# BMP180.net
KiCad netlist of a schematic drawn in Altium Designer
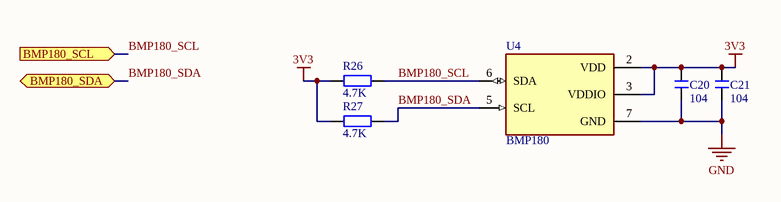
[diagram p0: BMP180气压传感器模块.SchDoc]

(export (version "E")
  (design (tool "Eeschema 10.0.6"))
  (components
    (comp (ref "C20")
      (value "104")
      (footprint "C 0603_L")
      (description "无极性贴片电容")
      (fields (field (name "版权归属") "黎明电子style"))
      (libsource (lib "3.3   - 电容capacitor") (part "C"))
    )
    (comp (ref "C21")
      (value "104")
      (footprint "C 0603_L")
      (description "无极性贴片电容")
      (fields (field (name "版权归属") "黎明电子style"))
      (libsource (lib "3.3   - 电容capacitor") (part "C"))
    )
    (comp (ref "R26")
      (value "4.7K")
      (footprint "R 0603_L")
      (description "贴片电阻")
      (fields (field (name "版权归属") "黎明电子style"))
      (libsource (lib "3.4   - 电阻Resistor") (part "R"))
    )
    (comp (ref "R27")
      (value "4.7K")
      (footprint "R 0603_L")
      (description "贴片电阻")
      (fields (field (name "版权归属") "黎明电子style"))
      (libsource (lib "3.4   - 电阻Resistor") (part "R"))
    )
    (comp (ref "U4")
      (value "BMP180")
      (footprint "LGA:LGA-7")
      (description "气压传感器Pressure Sensor 4.35PSI ~ 15.95PSI _30kPa ~ 110kPa_ Absolute 16 ~ 19 b 7-VLGA")
      (fields (field (name "MF") "Bosch Sensortec") (field (name "DIGI-KEY_PART_NUMBER") "828-1027-1-ND"))
      (libsource (lib "11.1 - 传感元件") (part "BMP180"))
    )
  )
  (nets
    (net (code "1") (name "/BMP180_SCL") (class "Default")
      (node (ref "R26") (pin "1") (pinfunction "1_1") (pintype "passive"))
      (node (ref "U4") (pin "6") (pinfunction "SDA_6") (pintype "bidirectional"))
    )
    (net (code "2") (name "/BMP180_SDA") (class "Default")
      (node (ref "R27") (pin "1") (pinfunction "1_1") (pintype "passive"))
      (node (ref "U4") (pin "5") (pinfunction "SCL_5") (pintype "input"))
    )
    (net (code "3") (name "3V3") (class "Default")
      (node (ref "C20") (pin "2") (pinfunction "2_2") (pintype "passive"))
      (node (ref "C21") (pin "2") (pinfunction "2_2") (pintype "passive"))
      (node (ref "R26") (pin "2") (pinfunction "2_2") (pintype "passive"))
      (node (ref "R27") (pin "2") (pinfunction "2_2") (pintype "passive"))
      (node (ref "U4") (pin "2") (pinfunction "VDD_2") (pintype "power_in"))
      (node (ref "U4") (pin "3") (pinfunction "VDDIO_3") (pintype "power_in"))
    )
    (net (code "4") (name "GND") (class "Default")
      (node (ref "C20") (pin "1") (pinfunction "1_1") (pintype "passive"))
      (node (ref "C21") (pin "1") (pinfunction "1_1") (pintype "passive"))
      (node (ref "U4") (pin "7") (pinfunction "GND_7") (pintype "power_in"))
    )
  )
)
